# RVPOVP.net
KiCad netlist of a schematic drawn in Altium Designer
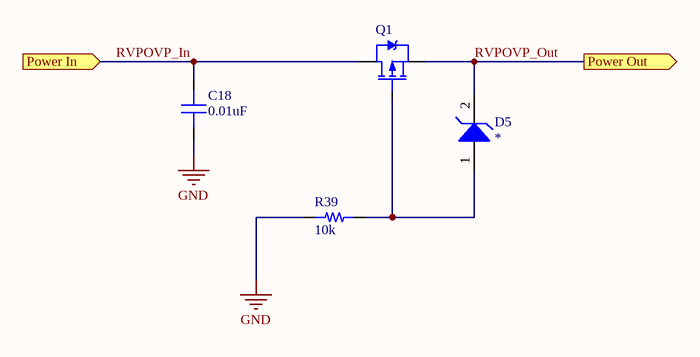
[diagram p0: RVPOVP.SchDoc]

(export (version "E")
  (design (tool "Eeschema 10.0.6"))
  (components
    (comp (ref "C18")
      (value "capacitor")
      (footprint "0603")
      (description "Generic 0603 capacitor")
      (fields (field (name "CAPACITANCE") "0.01uF") (field (name "VOLTAGE") "50"))
      (libsource (lib "altlib") (part "capacitor"))
    )
    (comp (ref "D5")
      (value "*")
      (footprint "SOD123F")
      (description "Zener Diode 14V 500mW ±5% Surface Mount SOD-1")
      (libsource (lib "altlib") (part "Zener"))
    )
    (comp (ref "Q1")
      (value "DMP3010LK3-13")
      (footprint "DMP3010LK3-13")
      (description "P-Channel MOSFET 30V 17A TO252")
      (fields (field (name "CREATEDBY") "Kevin"))
      (libsource (lib "altlib") (part "DMP3010LK3-13"))
    )
    (comp (ref "R39")
      (value "resistor")
      (footprint "0603")
      (fields (field (name "RESISTANCE") "10k"))
      (libsource (lib "altlib") (part "resistor"))
    )
  )
  (nets
    (net (code "1") (name "/RVPOVP_In") (class "Default")
      (node (ref "C18") (pin "2") (pinfunction "2_2") (pintype "passive"))
      (node (ref "Q1") (pin "3") (pinfunction "D_3") (pintype "passive"))
    )
    (net (code "2") (name "/RVPOVP_Out") (class "Default")
      (node (ref "D5") (pin "2") (pinfunction "K_2") (pintype "passive"))
      (node (ref "Q1") (pin "2") (pinfunction "S_2") (pintype "passive"))
    )
    (net (code "3") (name "GND") (class "Default")
      (node (ref "C18") (pin "1") (pinfunction "1_1") (pintype "passive"))
      (node (ref "R39") (pin "1") (pinfunction "1_1") (pintype "passive"))
    )
    (net (code "4") (name "Net-(D5-A)") (class "Default")
      (node (ref "D5") (pin "1") (pinfunction "A_1") (pintype "passive"))
      (node (ref "Q1") (pin "1") (pinfunction "G_1") (pintype "passive"))
      (node (ref "R39") (pin "2") (pinfunction "2_2") (pintype "passive"))
    )
  )
)
